# multiple_frequency_divider_1_0.net
KiCad netlist of a schematic drawn in EAGLE
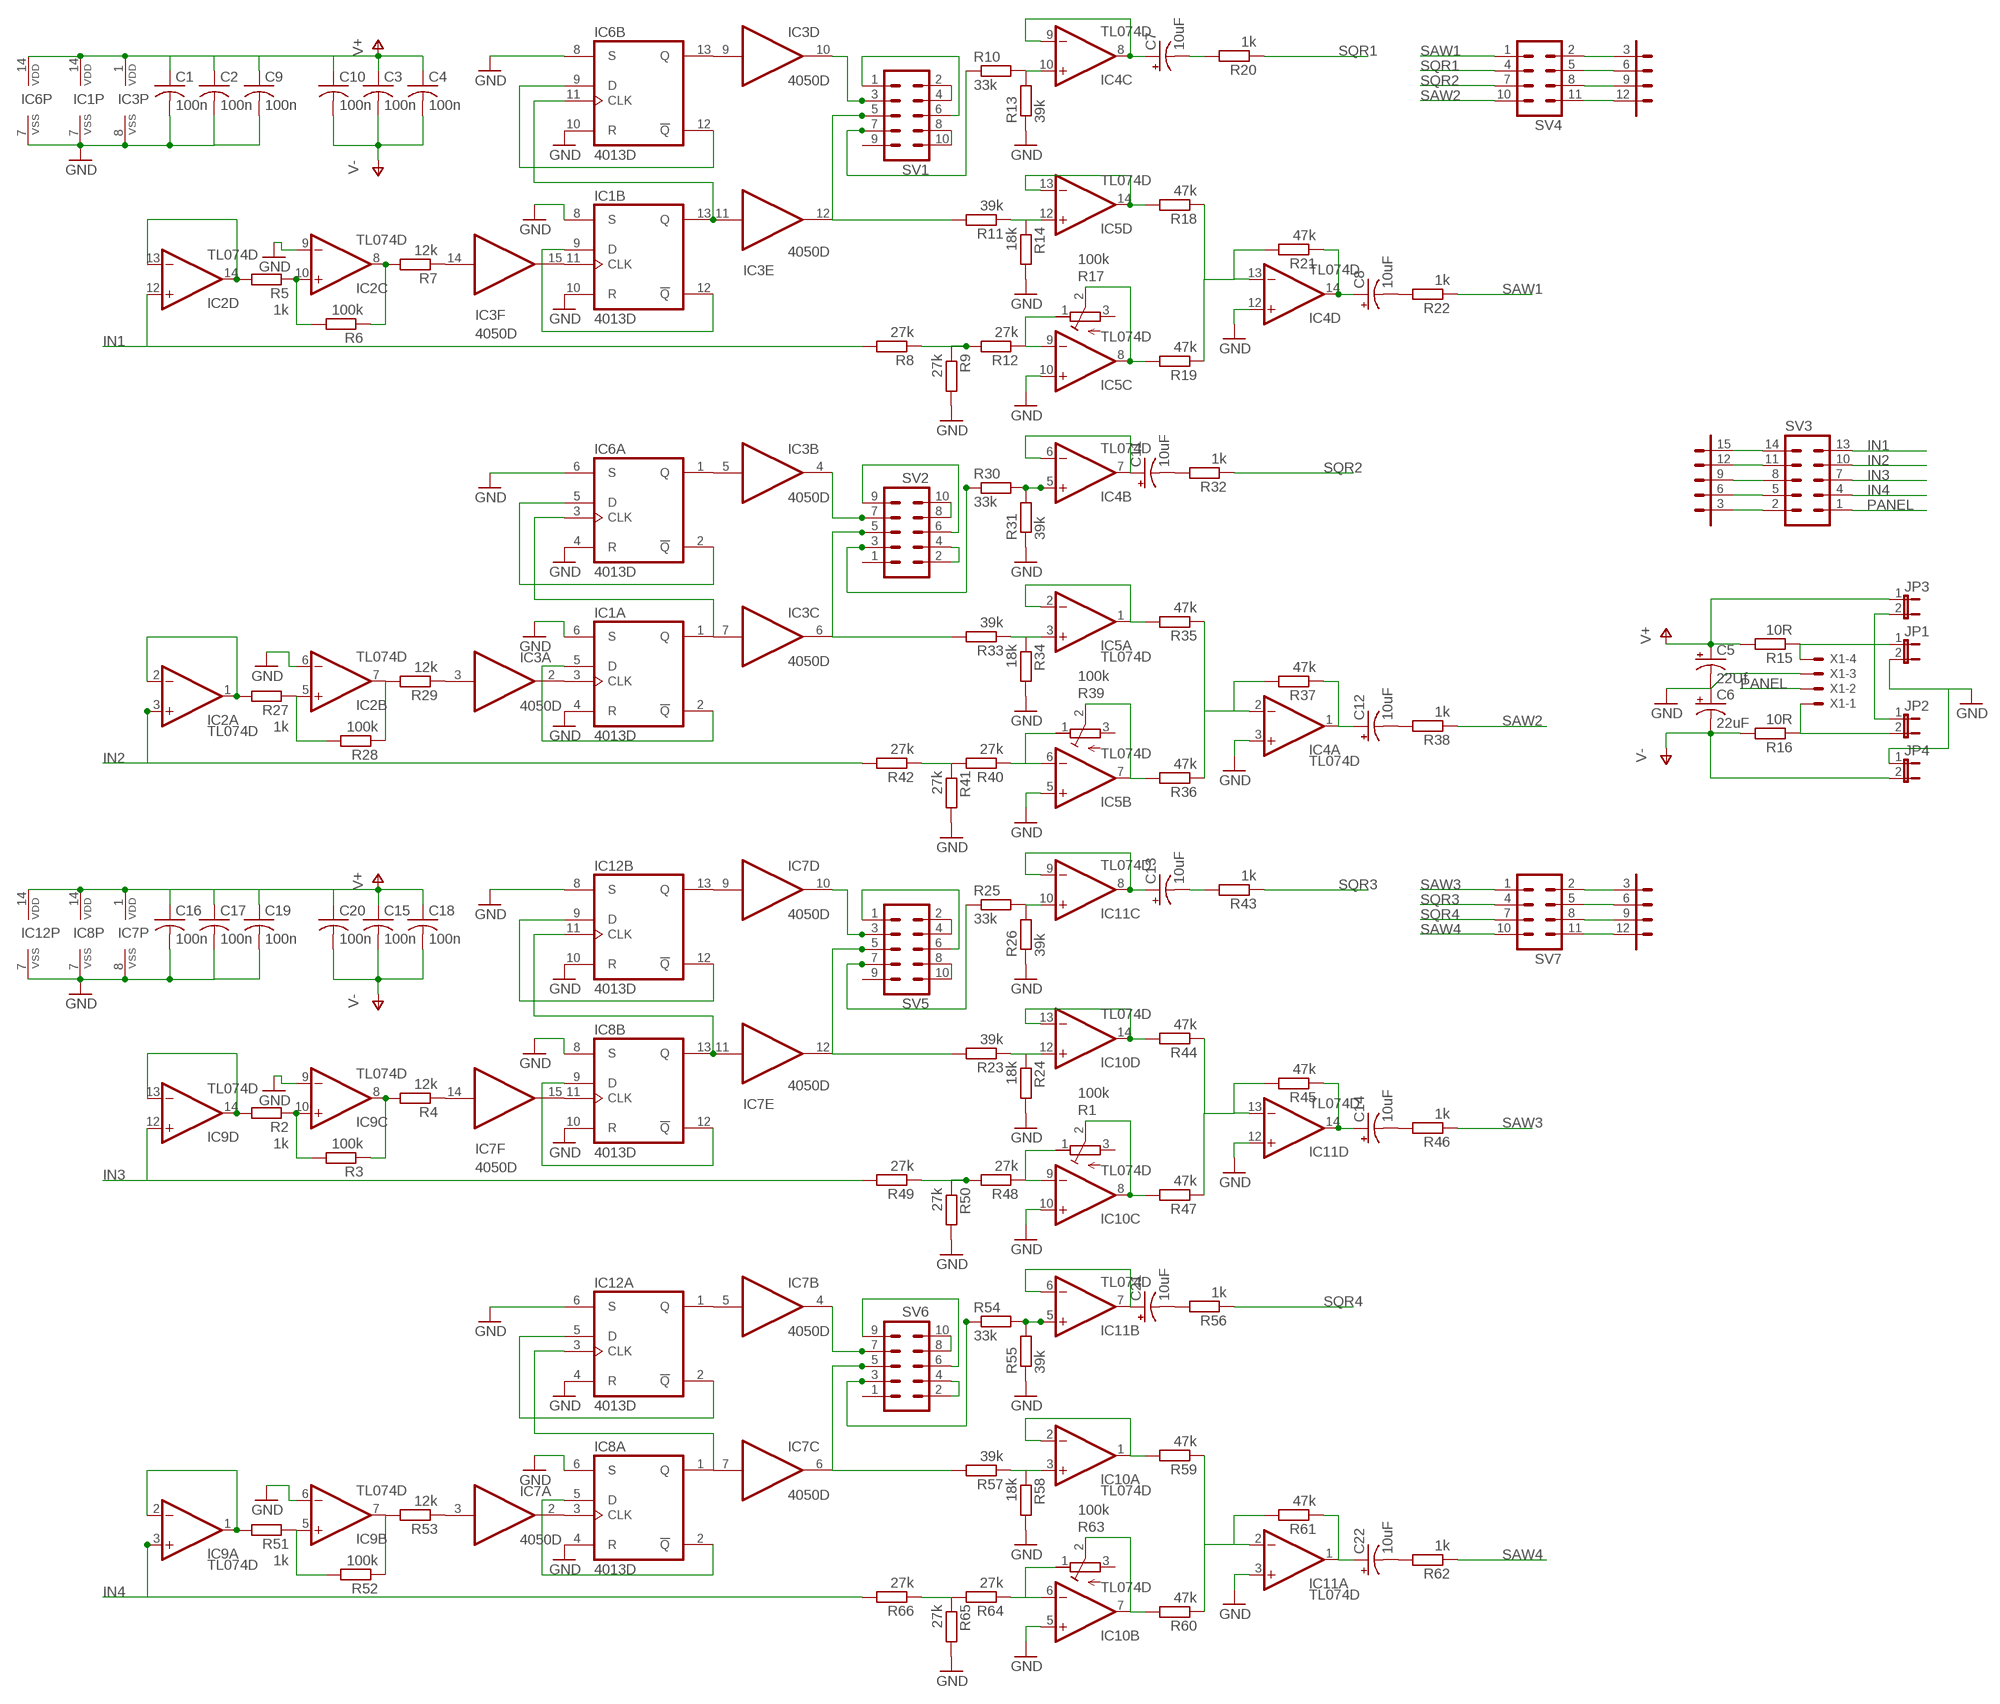
[diagram p0: schematic, sheet 1]

(export (version "E")
  (design (tool "Eeschema 10.0.6"))
  (components
    (comp (ref "C1")
      (value "100n")
      (footprint "eagle-import:C025-024X044")
      (libsource (lib "eagle-import") (part "C-US025-024X044"))
    )
    (comp (ref "C2")
      (value "100n")
      (footprint "eagle-import:C025-024X044")
      (libsource (lib "eagle-import") (part "C-US025-024X044"))
    )
    (comp (ref "C3")
      (value "100n")
      (footprint "eagle-import:C025-024X044")
      (libsource (lib "eagle-import") (part "C-US025-024X044"))
    )
    (comp (ref "C4")
      (value "100n")
      (footprint "eagle-import:C025-024X044")
      (libsource (lib "eagle-import") (part "C-US025-024X044"))
    )
    (comp (ref "C5")
      (value "22Uf")
      (footprint "eagle-import:E2,5-5")
      (libsource (lib "eagle-import") (part "CPOL-USE2.5-5"))
    )
    (comp (ref "C6")
      (value "22uF")
      (footprint "eagle-import:E2,5-5")
      (libsource (lib "eagle-import") (part "CPOL-USE2.5-5"))
    )
    (comp (ref "C7")
      (value "10uF")
      (footprint "eagle-import:E2,5-5")
      (libsource (lib "eagle-import") (part "CPOL-USE2.5-5"))
    )
    (comp (ref "C8")
      (value "10uF")
      (footprint "eagle-import:E2,5-5")
      (libsource (lib "eagle-import") (part "CPOL-USE2.5-5"))
    )
    (comp (ref "C9")
      (value "100n")
      (footprint "eagle-import:C025-024X044")
      (libsource (lib "eagle-import") (part "C-US025-024X044"))
    )
    (comp (ref "C10")
      (value "100n")
      (footprint "eagle-import:C025-024X044")
      (libsource (lib "eagle-import") (part "C-US025-024X044"))
    )
    (comp (ref "C11")
      (value "10uF")
      (footprint "eagle-import:E2,5-5")
      (libsource (lib "eagle-import") (part "CPOL-USE2.5-5"))
    )
    (comp (ref "C12")
      (value "10uF")
      (footprint "eagle-import:E2,5-5")
      (libsource (lib "eagle-import") (part "CPOL-USE2.5-5"))
    )
    (comp (ref "C13")
      (value "10uF")
      (footprint "eagle-import:E2,5-5")
      (libsource (lib "eagle-import") (part "CPOL-USE2.5-5"))
    )
    (comp (ref "C14")
      (value "10uF")
      (footprint "eagle-import:E2,5-5")
      (libsource (lib "eagle-import") (part "CPOL-USE2.5-5"))
    )
    (comp (ref "C15")
      (value "100n")
      (footprint "eagle-import:C025-024X044")
      (libsource (lib "eagle-import") (part "C-US025-024X044"))
    )
    (comp (ref "C16")
      (value "100n")
      (footprint "eagle-import:C025-024X044")
      (libsource (lib "eagle-import") (part "C-US025-024X044"))
    )
    (comp (ref "C17")
      (value "100n")
      (footprint "eagle-import:C025-024X044")
      (libsource (lib "eagle-import") (part "C-US025-024X044"))
    )
    (comp (ref "C18")
      (value "100n")
      (footprint "eagle-import:C025-024X044")
      (libsource (lib "eagle-import") (part "C-US025-024X044"))
    )
    (comp (ref "C19")
      (value "100n")
      (footprint "eagle-import:C025-024X044")
      (libsource (lib "eagle-import") (part "C-US025-024X044"))
    )
    (comp (ref "C20")
      (value "100n")
      (footprint "eagle-import:C025-024X044")
      (libsource (lib "eagle-import") (part "C-US025-024X044"))
    )
    (comp (ref "C21")
      (value "10uF")
      (footprint "eagle-import:E2,5-5")
      (libsource (lib "eagle-import") (part "CPOL-USE2.5-5"))
    )
    (comp (ref "C22")
      (value "10uF")
      (footprint "eagle-import:E2,5-5")
      (libsource (lib "eagle-import") (part "CPOL-USE2.5-5"))
    )
    (comp (ref "IC1")
      (value "4013D")
      (footprint "eagle-import:SO14")
      (libsource (lib "eagle-import") (part "4013D"))
    )
    (comp (ref "IC2")
      (value "TL074D")
      (footprint "eagle-import:SO14")
      (libsource (lib "eagle-import") (part "TL074D"))
    )
    (comp (ref "IC3")
      (value "4050D")
      (footprint "eagle-import:SO16")
      (libsource (lib "eagle-import") (part "4050D"))
    )
    (comp (ref "IC4")
      (value "TL074D")
      (footprint "eagle-import:SO14")
      (libsource (lib "eagle-import") (part "TL074D"))
    )
    (comp (ref "IC5")
      (value "TL074D")
      (footprint "eagle-import:SO14")
      (libsource (lib "eagle-import") (part "TL074D"))
    )
    (comp (ref "IC6")
      (value "4013D")
      (footprint "eagle-import:SO14")
      (libsource (lib "eagle-import") (part "4013D"))
    )
    (comp (ref "IC7")
      (value "4050D")
      (footprint "eagle-import:SO16")
      (libsource (lib "eagle-import") (part "4050D"))
    )
    (comp (ref "IC8")
      (value "4013D")
      (footprint "eagle-import:SO14")
      (libsource (lib "eagle-import") (part "4013D"))
    )
    (comp (ref "IC9")
      (value "TL074D")
      (footprint "eagle-import:SO14")
      (libsource (lib "eagle-import") (part "TL074D"))
    )
    (comp (ref "IC10")
      (value "TL074D")
      (footprint "eagle-import:SO14")
      (libsource (lib "eagle-import") (part "TL074D"))
    )
    (comp (ref "IC11")
      (value "TL074D")
      (footprint "eagle-import:SO14")
      (libsource (lib "eagle-import") (part "TL074D"))
    )
    (comp (ref "IC12")
      (value "4013D")
      (footprint "eagle-import:SO14")
      (libsource (lib "eagle-import") (part "4013D"))
    )
    (comp (ref "JP1")
      (value "JP1E")
      (footprint "eagle-import:JP1")
      (libsource (lib "eagle-import") (part "JP1E"))
    )
    (comp (ref "JP2")
      (value "JP1E")
      (footprint "eagle-import:JP1")
      (libsource (lib "eagle-import") (part "JP1E"))
    )
    (comp (ref "JP3")
      (value "JP1E")
      (footprint "eagle-import:JP1")
      (libsource (lib "eagle-import") (part "JP1E"))
    )
    (comp (ref "JP4")
      (value "JP1E")
      (footprint "eagle-import:JP1")
      (libsource (lib "eagle-import") (part "JP1E"))
    )
    (comp (ref "R1")
      (value "100k")
      (footprint "eagle-import:RTRIMT93YA")
      (libsource (lib "eagle-import") (part "R-TRIMMT93YA"))
    )
    (comp (ref "R2")
      (value "1k")
      (footprint "eagle-import:0204_5")
      (libsource (lib "eagle-import") (part "R-EU_0204/5"))
    )
    (comp (ref "R3")
      (value "100k")
      (footprint "eagle-import:0204_5")
      (libsource (lib "eagle-import") (part "R-EU_0204/5"))
    )
    (comp (ref "R4")
      (value "12k")
      (footprint "eagle-import:0204_5")
      (libsource (lib "eagle-import") (part "R-EU_0204/5"))
    )
    (comp (ref "R5")
      (value "1k")
      (footprint "eagle-import:0204_5")
      (libsource (lib "eagle-import") (part "R-EU_0204/5"))
    )
    (comp (ref "R6")
      (value "100k")
      (footprint "eagle-import:0204_5")
      (libsource (lib "eagle-import") (part "R-EU_0204/5"))
    )
    (comp (ref "R7")
      (value "12k")
      (footprint "eagle-import:0204_5")
      (libsource (lib "eagle-import") (part "R-EU_0204/5"))
    )
    (comp (ref "R8")
      (value "27k")
      (footprint "eagle-import:0204_5")
      (libsource (lib "eagle-import") (part "R-EU_0204/5"))
    )
    (comp (ref "R9")
      (value "27k")
      (footprint "eagle-import:0204_5")
      (libsource (lib "eagle-import") (part "R-EU_0204/5"))
    )
    (comp (ref "R10")
      (value "33k")
      (footprint "eagle-import:0204_5")
      (libsource (lib "eagle-import") (part "R-EU_0204/5"))
    )
    (comp (ref "R11")
      (value "39k")
      (footprint "eagle-import:0204_5")
      (libsource (lib "eagle-import") (part "R-EU_0204/5"))
    )
    (comp (ref "R12")
      (value "27k")
      (footprint "eagle-import:0204_5")
      (libsource (lib "eagle-import") (part "R-EU_0204/5"))
    )
    (comp (ref "R13")
      (value "39k")
      (footprint "eagle-import:0204_5")
      (libsource (lib "eagle-import") (part "R-EU_0204/5"))
    )
    (comp (ref "R14")
      (value "18k")
      (footprint "eagle-import:0204_5")
      (libsource (lib "eagle-import") (part "R-EU_0204/5"))
    )
    (comp (ref "R15")
      (value "10R")
      (footprint "eagle-import:0204_5")
      (libsource (lib "eagle-import") (part "R-EU_0204/5"))
    )
    (comp (ref "R16")
      (value "10R")
      (footprint "eagle-import:0204_5")
      (libsource (lib "eagle-import") (part "R-EU_0204/5"))
    )
    (comp (ref "R17")
      (value "100k")
      (footprint "eagle-import:RTRIMT93YA")
      (libsource (lib "eagle-import") (part "R-TRIMMT93YA"))
    )
    (comp (ref "R18")
      (value "47k")
      (footprint "eagle-import:0204_5")
      (libsource (lib "eagle-import") (part "R-EU_0204/5"))
    )
    (comp (ref "R19")
      (value "47k")
      (footprint "eagle-import:0204_5")
      (libsource (lib "eagle-import") (part "R-EU_0204/5"))
    )
    (comp (ref "R20")
      (value "1k")
      (footprint "eagle-import:0204_5")
      (libsource (lib "eagle-import") (part "R-EU_0204/5"))
    )
    (comp (ref "R21")
      (value "47k")
      (footprint "eagle-import:0204_5")
      (libsource (lib "eagle-import") (part "R-EU_0204/5"))
    )
    (comp (ref "R22")
      (value "1k")
      (footprint "eagle-import:0204_5")
      (libsource (lib "eagle-import") (part "R-EU_0204/5"))
    )
    (comp (ref "R23")
      (value "39k")
      (footprint "eagle-import:0204_5")
      (libsource (lib "eagle-import") (part "R-EU_0204/5"))
    )
    (comp (ref "R24")
      (value "18k")
      (footprint "eagle-import:0204_5")
      (libsource (lib "eagle-import") (part "R-EU_0204/5"))
    )
    (comp (ref "R25")
      (value "33k")
      (footprint "eagle-import:0204_5")
      (libsource (lib "eagle-import") (part "R-EU_0204/5"))
    )
    (comp (ref "R26")
      (value "39k")
      (footprint "eagle-import:0204_5")
      (libsource (lib "eagle-import") (part "R-EU_0204/5"))
    )
    (comp (ref "R27")
      (value "1k")
      (footprint "eagle-import:0204_5")
      (libsource (lib "eagle-import") (part "R-EU_0204/5"))
    )
    (comp (ref "R28")
      (value "100k")
      (footprint "eagle-import:0204_5")
      (libsource (lib "eagle-import") (part "R-EU_0204/5"))
    )
    (comp (ref "R29")
      (value "12k")
      (footprint "eagle-import:0204_5")
      (libsource (lib "eagle-import") (part "R-EU_0204/5"))
    )
    (comp (ref "R30")
      (value "33k")
      (footprint "eagle-import:0204_5")
      (libsource (lib "eagle-import") (part "R-EU_0204/5"))
    )
    (comp (ref "R31")
      (value "39k")
      (footprint "eagle-import:0204_5")
      (libsource (lib "eagle-import") (part "R-EU_0204/5"))
    )
    (comp (ref "R32")
      (value "1k")
      (footprint "eagle-import:0204_5")
      (libsource (lib "eagle-import") (part "R-EU_0204/5"))
    )
    (comp (ref "R33")
      (value "39k")
      (footprint "eagle-import:0204_5")
      (libsource (lib "eagle-import") (part "R-EU_0204/5"))
    )
    (comp (ref "R34")
      (value "18k")
      (footprint "eagle-import:0204_5")
      (libsource (lib "eagle-import") (part "R-EU_0204/5"))
    )
    (comp (ref "R35")
      (value "47k")
      (footprint "eagle-import:0204_5")
      (libsource (lib "eagle-import") (part "R-EU_0204/5"))
    )
    (comp (ref "R36")
      (value "47k")
      (footprint "eagle-import:0204_5")
      (libsource (lib "eagle-import") (part "R-EU_0204/5"))
    )
    (comp (ref "R37")
      (value "47k")
      (footprint "eagle-import:0204_5")
      (libsource (lib "eagle-import") (part "R-EU_0204/5"))
    )
    (comp (ref "R38")
      (value "1k")
      (footprint "eagle-import:0204_5")
      (libsource (lib "eagle-import") (part "R-EU_0204/5"))
    )
    (comp (ref "R39")
      (value "100k")
      (footprint "eagle-import:RTRIMT93YA")
      (libsource (lib "eagle-import") (part "R-TRIMMT93YA"))
    )
    (comp (ref "R40")
      (value "27k")
      (footprint "eagle-import:0204_5")
      (libsource (lib "eagle-import") (part "R-EU_0204/5"))
    )
    (comp (ref "R41")
      (value "27k")
      (footprint "eagle-import:0204_5")
      (libsource (lib "eagle-import") (part "R-EU_0204/5"))
    )
    (comp (ref "R42")
      (value "27k")
      (footprint "eagle-import:0204_5")
      (libsource (lib "eagle-import") (part "R-EU_0204/5"))
    )
    (comp (ref "R43")
      (value "1k")
      (footprint "eagle-import:0204_5")
      (libsource (lib "eagle-import") (part "R-EU_0204/5"))
    )
    (comp (ref "R44")
      (value "47k")
      (footprint "eagle-import:0204_5")
      (libsource (lib "eagle-import") (part "R-EU_0204/5"))
    )
    (comp (ref "R45")
      (value "47k")
      (footprint "eagle-import:0204_5")
      (libsource (lib "eagle-import") (part "R-EU_0204/5"))
    )
    (comp (ref "R46")
      (value "1k")
      (footprint "eagle-import:0204_5")
      (libsource (lib "eagle-import") (part "R-EU_0204/5"))
    )
    (comp (ref "R47")
      (value "47k")
      (footprint "eagle-import:0204_5")
      (libsource (lib "eagle-import") (part "R-EU_0204/5"))
    )
    (comp (ref "R48")
      (value "27k")
      (footprint "eagle-import:0204_5")
      (libsource (lib "eagle-import") (part "R-EU_0204/5"))
    )
    (comp (ref "R49")
      (value "27k")
      (footprint "eagle-import:0204_5")
      (libsource (lib "eagle-import") (part "R-EU_0204/5"))
    )
    (comp (ref "R50")
      (value "27k")
      (footprint "eagle-import:0204_5")
      (libsource (lib "eagle-import") (part "R-EU_0204/5"))
    )
    (comp (ref "R51")
      (value "1k")
      (footprint "eagle-import:0204_5")
      (libsource (lib "eagle-import") (part "R-EU_0204/5"))
    )
    (comp (ref "R52")
      (value "100k")
      (footprint "eagle-import:0204_5")
      (libsource (lib "eagle-import") (part "R-EU_0204/5"))
    )
    (comp (ref "R53")
      (value "12k")
      (footprint "eagle-import:0204_5")
      (libsource (lib "eagle-import") (part "R-EU_0204/5"))
    )
    (comp (ref "R54")
      (value "33k")
      (footprint "eagle-import:0204_5")
      (libsource (lib "eagle-import") (part "R-EU_0204/5"))
    )
    (comp (ref "R55")
      (value "39k")
      (footprint "eagle-import:0204_5")
      (libsource (lib "eagle-import") (part "R-EU_0204/5"))
    )
    (comp (ref "R56")
      (value "1k")
      (footprint "eagle-import:0204_5")
      (libsource (lib "eagle-import") (part "R-EU_0204/5"))
    )
    (comp (ref "R57")
      (value "39k")
      (footprint "eagle-import:0204_5")
      (libsource (lib "eagle-import") (part "R-EU_0204/5"))
    )
    (comp (ref "R58")
      (value "18k")
      (footprint "eagle-import:0204_5")
      (libsource (lib "eagle-import") (part "R-EU_0204/5"))
    )
    (comp (ref "R59")
      (value "47k")
      (footprint "eagle-import:0204_5")
      (libsource (lib "eagle-import") (part "R-EU_0204/5"))
    )
    (comp (ref "R60")
      (value "47k")
      (footprint "eagle-import:0204_5")
      (libsource (lib "eagle-import") (part "R-EU_0204/5"))
    )
    (comp (ref "R61")
      (value "47k")
      (footprint "eagle-import:0204_5")
      (libsource (lib "eagle-import") (part "R-EU_0204/5"))
    )
    (comp (ref "R62")
      (value "1k")
      (footprint "eagle-import:0204_5")
      (libsource (lib "eagle-import") (part "R-EU_0204/5"))
    )
    (comp (ref "R63")
      (value "100k")
      (footprint "eagle-import:RTRIMT93YA")
      (libsource (lib "eagle-import") (part "R-TRIMMT93YA"))
    )
    (comp (ref "R64")
      (value "27k")
      (footprint "eagle-import:0204_5")
      (libsource (lib "eagle-import") (part "R-EU_0204/5"))
    )
    (comp (ref "R65")
      (value "27k")
      (footprint "eagle-import:0204_5")
      (libsource (lib "eagle-import") (part "R-EU_0204/5"))
    )
    (comp (ref "R66")
      (value "27k")
      (footprint "eagle-import:0204_5")
      (libsource (lib "eagle-import") (part "R-EU_0204/5"))
    )
    (comp (ref "SV1")
      (value "MA05-2")
      (footprint "eagle-import:MA05-2")
      (libsource (lib "eagle-import") (part "MA05-2"))
    )
    (comp (ref "SV2")
      (value "MA05-2")
      (footprint "eagle-import:MA05-2")
      (libsource (lib "eagle-import") (part "MA05-2"))
    )
    (comp (ref "SV3")
      (value "MA05-3")
      (footprint "eagle-import:MA05-3")
      (libsource (lib "eagle-import") (part "MA05-3"))
    )
    (comp (ref "SV4")
      (value "MA04-3")
      (footprint "eagle-import:MA04-3")
      (libsource (lib "eagle-import") (part "MA04-3"))
    )
    (comp (ref "SV5")
      (value "MA05-2")
      (footprint "eagle-import:MA05-2")
      (libsource (lib "eagle-import") (part "MA05-2"))
    )
    (comp (ref "SV6")
      (value "MA05-2")
      (footprint "eagle-import:MA05-2")
      (libsource (lib "eagle-import") (part "MA05-2"))
    )
    (comp (ref "SV7")
      (value "MA04-3")
      (footprint "eagle-import:MA04-3")
      (libsource (lib "eagle-import") (part "MA04-3"))
    )
    (comp (ref "X1")
      (value "KK-156-4")
      (footprint "eagle-import:KK-156-4")
      (libsource (lib "eagle-import") (part "KK-156-4"))
    )
  )
  (nets
    (net (code "1") (name "/IN1") (class "Default")
      (node (ref "IC2") (pin "12") (pinfunction "+IN_12") (pintype "input"))
      (node (ref "R8") (pin "2") (pinfunction "2_2") (pintype "passive"))
      (node (ref "SV3") (pin "13") (pinfunction "13_13") (pintype "passive"))
    )
    (net (code "2") (name "/IN2") (class "Default")
      (node (ref "IC2") (pin "3") (pinfunction "+IN_3") (pintype "input"))
      (node (ref "R42") (pin "2") (pinfunction "2_2") (pintype "passive"))
      (node (ref "SV3") (pin "10") (pinfunction "10_10") (pintype "passive"))
    )
    (net (code "3") (name "/IN3") (class "Default")
      (node (ref "IC9") (pin "12") (pinfunction "+IN_12") (pintype "input"))
      (node (ref "R49") (pin "2") (pinfunction "2_2") (pintype "passive"))
      (node (ref "SV3") (pin "7") (pinfunction "7_7") (pintype "passive"))
    )
    (net (code "4") (name "/IN4") (class "Default")
      (node (ref "IC9") (pin "3") (pinfunction "+IN_3") (pintype "input"))
      (node (ref "R66") (pin "2") (pinfunction "2_2") (pintype "passive"))
      (node (ref "SV3") (pin "4") (pinfunction "4_4") (pintype "passive"))
    )
    (net (code "5") (name "/PANEL") (class "Default")
      (node (ref "JP2") (pin "1") (pinfunction "1_1") (pintype "passive"))
      (node (ref "JP3") (pin "2") (pinfunction "2_2") (pintype "passive"))
      (node (ref "SV3") (pin "1") (pinfunction "1_1") (pintype "passive"))
      (node (ref "X1") (pin "2") (pinfunction "S_2") (pintype "passive"))
    )
    (net (code "6") (name "/SAW1") (class "Default")
      (node (ref "R22") (pin "1") (pinfunction "1_1") (pintype "passive"))
      (node (ref "SV4") (pin "1") (pinfunction "1_1") (pintype "passive"))
    )
    (net (code "7") (name "/SAW2") (class "Default")
      (node (ref "R38") (pin "1") (pinfunction "1_1") (pintype "passive"))
      (node (ref "SV4") (pin "10") (pinfunction "10_10") (pintype "passive"))
    )
    (net (code "8") (name "/SAW3") (class "Default")
      (node (ref "R46") (pin "1") (pinfunction "1_1") (pintype "passive"))
      (node (ref "SV7") (pin "1") (pinfunction "1_1") (pintype "passive"))
    )
    (net (code "9") (name "/SAW4") (class "Default")
      (node (ref "R62") (pin "1") (pinfunction "1_1") (pintype "passive"))
      (node (ref "SV7") (pin "10") (pinfunction "10_10") (pintype "passive"))
    )
    (net (code "10") (name "/SQR1") (class "Default")
      (node (ref "R20") (pin "1") (pinfunction "1_1") (pintype "passive"))
      (node (ref "SV4") (pin "4") (pinfunction "4_4") (pintype "passive"))
    )
    (net (code "11") (name "/SQR2") (class "Default")
      (node (ref "R32") (pin "1") (pinfunction "1_1") (pintype "passive"))
      (node (ref "SV4") (pin "7") (pinfunction "7_7") (pintype "passive"))
    )
    (net (code "12") (name "/SQR3") (class "Default")
      (node (ref "R43") (pin "1") (pinfunction "1_1") (pintype "passive"))
      (node (ref "SV7") (pin "4") (pinfunction "4_4") (pintype "passive"))
    )
    (net (code "13") (name "/SQR4") (class "Default")
      (node (ref "R56") (pin "1") (pinfunction "1_1") (pintype "passive"))
      (node (ref "SV7") (pin "7") (pinfunction "7_7") (pintype "passive"))
    )
    (net (code "14") (name "GND") (class "Default")
      (node (ref "C1") (pin "2") (pinfunction "2_2") (pintype "passive"))
      (node (ref "C16") (pin "2") (pinfunction "2_2") (pintype "passive"))
      (node (ref "C17") (pin "2") (pinfunction "2_2") (pintype "passive"))
      (node (ref "C19") (pin "2") (pinfunction "2_2") (pintype "passive"))
      (node (ref "C2") (pin "2") (pinfunction "2_2") (pintype "passive"))
      (node (ref "C5") (pin "-") (pinfunction "-_-") (pintype "passive"))
      (node (ref "C6") (pin "+") (pinfunction "+_+") (pintype "passive"))
      (node (ref "C9") (pin "2") (pinfunction "2_2") (pintype "passive"))
      (node (ref "IC1") (pin "10") (pinfunction "R_10") (pintype "input"))
      (node (ref "IC1") (pin "4") (pinfunction "R_4") (pintype "input"))
      (node (ref "IC1") (pin "6") (pinfunction "S_6") (pintype "input"))
      (node (ref "IC1") (pin "7") (pinfunction "VSS_7") (pintype "power_in"))
      (node (ref "IC1") (pin "8") (pinfunction "S_8") (pintype "input"))
      (node (ref "IC10") (pin "10") (pinfunction "+IN_10") (pintype "input"))
      (node (ref "IC10") (pin "5") (pinfunction "+IN_5") (pintype "input"))
      (node (ref "IC11") (pin "12") (pinfunction "+IN_12") (pintype "input"))
      (node (ref "IC11") (pin "3") (pinfunction "+IN_3") (pintype "input"))
      (node (ref "IC12") (pin "10") (pinfunction "R_10") (pintype "input"))
      (node (ref "IC12") (pin "4") (pinfunction "R_4") (pintype "input"))
      (node (ref "IC12") (pin "6") (pinfunction "S_6") (pintype "input"))
      (node (ref "IC12") (pin "7") (pinfunction "VSS_7") (pintype "power_in"))
      (node (ref "IC12") (pin "8") (pinfunction "S_8") (pintype "input"))
      (node (ref "IC2") (pin "6") (pinfunction "-IN_6") (pintype "input"))
      (node (ref "IC2") (pin "9") (pinfunction "-IN_9") (pintype "input"))
      (node (ref "IC3") (pin "8") (pinfunction "VSS_8") (pintype "power_in"))
      (node (ref "IC4") (pin "12") (pinfunction "+IN_12") (pintype "input"))
      (node (ref "IC4") (pin "3") (pinfunction "+IN_3") (pintype "input"))
      (node (ref "IC5") (pin "10") (pinfunction "+IN_10") (pintype "input"))
      (node (ref "IC5") (pin "5") (pinfunction "+IN_5") (pintype "input"))
      (node (ref "IC6") (pin "10") (pinfunction "R_10") (pintype "input"))
      (node (ref "IC6") (pin "4") (pinfunction "R_4") (pintype "input"))
      (node (ref "IC6") (pin "6") (pinfunction "S_6") (pintype "input"))
      (node (ref "IC6") (pin "7") (pinfunction "VSS_7") (pintype "power_in"))
      (node (ref "IC6") (pin "8") (pinfunction "S_8") (pintype "input"))
      (node (ref "IC7") (pin "8") (pinfunction "VSS_8") (pintype "power_in"))
      (node (ref "IC8") (pin "10") (pinfunction "R_10") (pintype "input"))
      (node (ref "IC8") (pin "4") (pinfunction "R_4") (pintype "input"))
      (node (ref "IC8") (pin "6") (pinfunction "S_6") (pintype "input"))
      (node (ref "IC8") (pin "7") (pinfunction "VSS_7") (pintype "power_in"))
      (node (ref "IC8") (pin "8") (pinfunction "S_8") (pintype "input"))
      (node (ref "IC9") (pin "6") (pinfunction "-IN_6") (pintype "input"))
      (node (ref "IC9") (pin "9") (pinfunction "-IN_9") (pintype "input"))
      (node (ref "JP1") (pin "2") (pinfunction "2_2") (pintype "passive"))
      (node (ref "JP4") (pin "1") (pinfunction "1_1") (pintype "passive"))
      (node (ref "R13") (pin "1") (pinfunction "1_1") (pintype "passive"))
      (node (ref "R14") (pin "2") (pinfunction "2_2") (pintype "passive"))
      (node (ref "R24") (pin "2") (pinfunction "2_2") (pintype "passive"))
      (node (ref "R26") (pin "1") (pinfunction "1_1") (pintype "passive"))
      (node (ref "R31") (pin "1") (pinfunction "1_1") (pintype "passive"))
      (node (ref "R34") (pin "2") (pinfunction "2_2") (pintype "passive"))
      (node (ref "R41") (pin "2") (pinfunction "2_2") (pintype "passive"))
      (node (ref "R50") (pin "2") (pinfunction "2_2") (pintype "passive"))
      (node (ref "R55") (pin "1") (pinfunction "1_1") (pintype "passive"))
      (node (ref "R58") (pin "2") (pinfunction "2_2") (pintype "passive"))
      (node (ref "R65") (pin "2") (pinfunction "2_2") (pintype "passive"))
      (node (ref "R9") (pin "2") (pinfunction "2_2") (pintype "passive"))
      (node (ref "X1") (pin "3") (pinfunction "S_3") (pintype "passive"))
    )
    (net (code "15") (name "Net-(C7-Pad-)") (class "Default")
      (node (ref "C7") (pin "-") (pinfunction "-_-") (pintype "passive"))
      (node (ref "R20") (pin "2") (pinfunction "2_2") (pintype "passive"))
    )
    (net (code "16") (name "Net-(C8-Pad-)") (class "Default")
      (node (ref "C8") (pin "-") (pinfunction "-_-") (pintype "passive"))
      (node (ref "R22") (pin "2") (pinfunction "2_2") (pintype "passive"))
    )
    (net (code "17") (name "Net-(C11-Pad-)") (class "Default")
      (node (ref "C11") (pin "-") (pinfunction "-_-") (pintype "passive"))
      (node (ref "R32") (pin "2") (pinfunction "2_2") (pintype "passive"))
    )
    (net (code "18") (name "Net-(C12-Pad-)") (class "Default")
      (node (ref "C12") (pin "-") (pinfunction "-_-") (pintype "passive"))
      (node (ref "R38") (pin "2") (pinfunction "2_2") (pintype "passive"))
    )
    (net (code "19") (name "Net-(C13-Pad-)") (class "Default")
      (node (ref "C13") (pin "-") (pinfunction "-_-") (pintype "passive"))
      (node (ref "R43") (pin "2") (pinfunction "2_2") (pintype "passive"))
    )
    (net (code "20") (name "Net-(C14-Pad-)") (class "Default")
      (node (ref "C14") (pin "-") (pinfunction "-_-") (pintype "passive"))
      (node (ref "R46") (pin "2") (pinfunction "2_2") (pintype "passive"))
    )
    (net (code "21") (name "Net-(C21-Pad-)") (class "Default")
      (node (ref "C21") (pin "-") (pinfunction "-_-") (pintype "passive"))
      (node (ref "R56") (pin "2") (pinfunction "2_2") (pintype "passive"))
    )
    (net (code "22") (name "Net-(C22-Pad-)") (class "Default")
      (node (ref "C22") (pin "-") (pinfunction "-_-") (pintype "passive"))
      (node (ref "R62") (pin "2") (pinfunction "2_2") (pintype "passive"))
    )
    (net (code "23") (name "Net-(IC1A-CLK)") (class "Default")
      (node (ref "IC1") (pin "3") (pinfunction "CLK_3") (pintype "input"))
      (node (ref "IC3") (pin "2") (pinfunction "O_2") (pintype "output"))
    )
    (net (code "24") (name "Net-(IC1A-D)") (class "Default")
      (node (ref "IC1") (pin "2") (pinfunction "~{Q}_2") (pintype "output"))
      (node (ref "IC1") (pin "5") (pinfunction "D_5") (pintype "input"))
    )
    (net (code "25") (name "Net-(IC1A-Q)") (class "Default")
      (node (ref "IC1") (pin "1") (pinfunction "Q_1") (pintype "output"))
      (node (ref "IC3") (pin "7") (pinfunction "I_7") (pintype "input"))
      (node (ref "IC6") (pin "3") (pinfunction "CLK_3") (pintype "input"))
    )
    (net (code "26") (name "Net-(IC1B-CLK)") (class "Default")
      (node (ref "IC1") (pin "11") (pinfunction "CLK_11") (pintype "input"))
      (node (ref "IC3") (pin "15") (pinfunction "O_15") (pintype "output"))
    )
    (net (code "27") (name "Net-(IC1B-D)") (class "Default")
      (node (ref "IC1") (pin "12") (pinfunction "~{Q}_12") (pintype "output"))
      (node (ref "IC1") (pin "9") (pinfunction "D_9") (pintype "input"))
    )
    (net (code "28") (name "Net-(IC1B-Q)") (class "Default")
      (node (ref "IC1") (pin "13") (pinfunction "Q_13") (pintype "output"))
      (node (ref "IC3") (pin "11") (pinfunction "I_11") (pintype "input"))
      (node (ref "IC6") (pin "11") (pinfunction "CLK_11") (pintype "input"))
    )
    (net (code "29") (name "Net-(IC2A--IN)") (class "Default")
      (node (ref "IC2") (pin "1") (pinfunction "OUT_1") (pintype "output"))
      (node (ref "IC2") (pin "2") (pinfunction "-IN_2") (pintype "input"))
      (node (ref "R27") (pin "2") (pinfunction "2_2") (pintype "passive"))
    )
    (net (code "30") (name "Net-(IC2B-+IN)") (class "Default")
      (node (ref "IC2") (pin "5") (pinfunction "+IN_5") (pintype "input"))
      (node (ref "R27") (pin "1") (pinfunction "1_1") (pintype "passive"))
      (node (ref "R28") (pin "2") (pinfunction "2_2") (pintype "passive"))
    )
    (net (code "31") (name "Net-(IC2B-OUT)") (class "Default")
      (node (ref "IC2") (pin "7") (pinfunction "OUT_7") (pintype "output"))
      (node (ref "R28") (pin "1") (pinfunction "1_1") (pintype "passive"))
      (node (ref "R29") (pin "2") (pinfunction "2_2") (pintype "passive"))
    )
    (net (code "32") (name "Net-(IC2C-+IN)") (class "Default")
      (node (ref "IC2") (pin "10") (pinfunction "+IN_10") (pintype "input"))
      (node (ref "R5") (pin "1") (pinfunction "1_1") (pintype "passive"))
      (node (ref "R6") (pin "2") (pinfunction "2_2") (pintype "passive"))
    )
    (net (code "33") (name "Net-(IC2C-OUT)") (class "Default")
      (node (ref "IC2") (pin "8") (pinfunction "OUT_8") (pintype "output"))
      (node (ref "R6") (pin "1") (pinfunction "1_1") (pintype "passive"))
      (node (ref "R7") (pin "2") (pinfunction "2_2") (pintype "passive"))
    )
    (net (code "34") (name "Net-(IC2D--IN)") (class "Default")
      (node (ref "IC2") (pin "13") (pinfunction "-IN_13") (pintype "input"))
      (node (ref "IC2") (pin "14") (pinfunction "OUT_14") (pintype "output"))
      (node (ref "R5") (pin "2") (pinfunction "2_2") (pintype "passive"))
    )
    (net (code "35") (name "Net-(IC3A-I)") (class "Default")
      (node (ref "IC3") (pin "3") (pinfunction "I_3") (pintype "input"))
      (node (ref "R29") (pin "1") (pinfunction "1_1") (pintype "passive"))
    )
    (net (code "36") (name "Net-(IC3B-I)") (class "Default")
      (node (ref "IC3") (pin "5") (pinfunction "I_5") (pintype "input"))
      (node (ref "IC6") (pin "1") (pinfunction "Q_1") (pintype "output"))
    )
    (net (code "37") (name "Net-(IC3B-O)") (class "Default")
      (node (ref "IC3") (pin "4") (pinfunction "O_4") (pintype "output"))
      (node (ref "SV2") (pin "7") (pinfunction "7_7") (pintype "passive"))
    )
    (net (code "38") (name "Net-(IC3C-O)") (class "Default")
      (node (ref "IC3") (pin "6") (pinfunction "O_6") (pintype "output"))
      (node (ref "R33") (pin "2") (pinfunction "2_2") (pintype "passive"))
      (node (ref "SV2") (pin "5") (pinfunction "5_5") (pintype "passive"))
    )
    (net (code "39") (name "Net-(IC3D-I)") (class "Default")
      (node (ref "IC3") (pin "9") (pinfunction "I_9") (pintype "input"))
      (node (ref "IC6") (pin "13") (pinfunction "Q_13") (pintype "output"))
    )
    (net (code "40") (name "Net-(IC3D-O)") (class "Default")
      (node (ref "IC3") (pin "10") (pinfunction "O_10") (pintype "output"))
      (node (ref "SV1") (pin "3") (pinfunction "3_3") (pintype "passive"))
    )
    (net (code "41") (name "Net-(IC3E-O)") (class "Default")
      (node (ref "IC3") (pin "12") (pinfunction "O_12") (pintype "output"))
      (node (ref "R11") (pin "2") (pinfunction "2_2") (pintype "passive"))
      (node (ref "SV1") (pin "5") (pinfunction "5_5") (pintype "passive"))
    )
    (net (code "42") (name "Net-(IC3F-I)") (class "Default")
      (node (ref "IC3") (pin "14") (pinfunction "I_14") (pintype "input"))
      (node (ref "R7") (pin "1") (pinfunction "1_1") (pintype "passive"))
    )
    (net (code "43") (name "Net-(IC4A--IN)") (class "Default")
      (node (ref "IC4") (pin "2") (pinfunction "-IN_2") (pintype "input"))
      (node (ref "R35") (pin "1") (pinfunction "1_1") (pintype "passive"))
      (node (ref "R36") (pin "1") (pinfunction "1_1") (pintype "passive"))
      (node (ref "R37") (pin "2") (pinfunction "2_2") (pintype "passive"))
    )
    (net (code "44") (name "Net-(IC4A-OUT)") (class "Default")
      (node (ref "C12") (pin "+") (pinfunction "+_+") (pintype "passive"))
      (node (ref "IC4") (pin "1") (pinfunction "OUT_1") (pintype "output"))
      (node (ref "R37") (pin "1") (pinfunction "1_1") (pintype "passive"))
    )
    (net (code "45") (name "Net-(IC4B-+IN)") (class "Default")
      (node (ref "IC4") (pin "5") (pinfunction "+IN_5") (pintype "input"))
      (node (ref "R30") (pin "2") (pinfunction "2_2") (pintype "passive"))
      (node (ref "R31") (pin "2") (pinfunction "2_2") (pintype "passive"))
    )
    (net (code "46") (name "Net-(IC4B--IN)") (class "Default")
      (node (ref "C11") (pin "+") (pinfunction "+_+") (pintype "passive"))
      (node (ref "IC4") (pin "6") (pinfunction "-IN_6") (pintype "input"))
      (node (ref "IC4") (pin "7") (pinfunction "OUT_7") (pintype "output"))
    )
    (net (code "47") (name "Net-(IC4C-+IN)") (class "Default")
      (node (ref "IC4") (pin "10") (pinfunction "+IN_10") (pintype "input"))
      (node (ref "R10") (pin "2") (pinfunction "2_2") (pintype "passive"))
      (node (ref "R13") (pin "2") (pinfunction "2_2") (pintype "passive"))
    )
    (net (code "48") (name "Net-(IC4C--IN)") (class "Default")
      (node (ref "C7") (pin "+") (pinfunction "+_+") (pintype "passive"))
      (node (ref "IC4") (pin "8") (pinfunction "OUT_8") (pintype "output"))
      (node (ref "IC4") (pin "9") (pinfunction "-IN_9") (pintype "input"))
    )
    (net (code "49") (name "Net-(IC4D--IN)") (class "Default")
      (node (ref "IC4") (pin "13") (pinfunction "-IN_13") (pintype "input"))
      (node (ref "R18") (pin "1") (pinfunction "1_1") (pintype "passive"))
      (node (ref "R19") (pin "1") (pinfunction "1_1") (pintype "passive"))
      (node (ref "R21") (pin "2") (pinfunction "2_2") (pintype "passive"))
    )
    (net (code "50") (name "Net-(IC4D-OUT)") (class "Default")
      (node (ref "C8") (pin "+") (pinfunction "+_+") (pintype "passive"))
      (node (ref "IC4") (pin "14") (pinfunction "OUT_14") (pintype "output"))
      (node (ref "R21") (pin "1") (pinfunction "1_1") (pintype "passive"))
    )
    (net (code "51") (name "Net-(IC5A-+IN)") (class "Default")
      (node (ref "IC5") (pin "3") (pinfunction "+IN_3") (pintype "input"))
      (node (ref "R33") (pin "1") (pinfunction "1_1") (pintype "passive"))
      (node (ref "R34") (pin "1") (pinfunction "1_1") (pintype "passive"))
    )
    (net (code "52") (name "Net-(IC5A--IN)") (class "Default")
      (node (ref "IC5") (pin "1") (pinfunction "OUT_1") (pintype "output"))
      (node (ref "IC5") (pin "2") (pinfunction "-IN_2") (pintype "input"))
      (node (ref "R35") (pin "2") (pinfunction "2_2") (pintype "passive"))
    )
    (net (code "53") (name "Net-(IC5B--IN)") (class "Default")
      (node (ref "IC5") (pin "6") (pinfunction "-IN_6") (pintype "input"))
      (node (ref "R39") (pin "1") (pinfunction "A_1") (pintype "passive"))
      (node (ref "R40") (pin "1") (pinfunction "1_1") (pintype "passive"))
    )
    (net (code "54") (name "Net-(IC5B-OUT)") (class "Default")
      (node (ref "IC5") (pin "7") (pinfunction "OUT_7") (pintype "output"))
      (node (ref "R36") (pin "2") (pinfunction "2_2") (pintype "passive"))
      (node (ref "R39") (pin "2") (pinfunction "S_2") (pintype "passive"))
    )
    (net (code "55") (name "Net-(IC5C--IN)") (class "Default")
      (node (ref "IC5") (pin "9") (pinfunction "-IN_9") (pintype "input"))
      (node (ref "R12") (pin "1") (pinfunction "1_1") (pintype "passive"))
      (node (ref "R17") (pin "1") (pinfunction "A_1") (pintype "passive"))
    )
    (net (code "56") (name "Net-(IC5C-OUT)") (class "Default")
      (node (ref "IC5") (pin "8") (pinfunction "OUT_8") (pintype "output"))
      (node (ref "R17") (pin "2") (pinfunction "S_2") (pintype "passive"))
      (node (ref "R19") (pin "2") (pinfunction "2_2") (pintype "passive"))
    )
    (net (code "57") (name "Net-(IC5D-+IN)") (class "Default")
      (node (ref "IC5") (pin "12") (pinfunction "+IN_12") (pintype "input"))
      (node (ref "R11") (pin "1") (pinfunction "1_1") (pintype "passive"))
      (node (ref "R14") (pin "1") (pinfunction "1_1") (pintype "passive"))
    )
    (net (code "58") (name "Net-(IC5D--IN)") (class "Default")
      (node (ref "IC5") (pin "13") (pinfunction "-IN_13") (pintype "input"))
      (node (ref "IC5") (pin "14") (pinfunction "OUT_14") (pintype "output"))
      (node (ref "R18") (pin "2") (pinfunction "2_2") (pintype "passive"))
    )
    (net (code "59") (name "Net-(IC6A-D)") (class "Default")
      (node (ref "IC6") (pin "2") (pinfunction "~{Q}_2") (pintype "output"))
      (node (ref "IC6") (pin "5") (pinfunction "D_5") (pintype "input"))
    )
    (net (code "60") (name "Net-(IC6B-D)") (class "Default")
      (node (ref "IC6") (pin "12") (pinfunction "~{Q}_12") (pintype "output"))
      (node (ref "IC6") (pin "9") (pinfunction "D_9") (pintype "input"))
    )
    (net (code "61") (name "Net-(IC7A-I)") (class "Default")
      (node (ref "IC7") (pin "3") (pinfunction "I_3") (pintype "input"))
      (node (ref "R53") (pin "1") (pinfunction "1_1") (pintype "passive"))
    )
    (net (code "62") (name "Net-(IC7A-O)") (class "Default")
      (node (ref "IC7") (pin "2") (pinfunction "O_2") (pintype "output"))
      (node (ref "IC8") (pin "3") (pinfunction "CLK_3") (pintype "input"))
    )
    (net (code "63") (name "Net-(IC7B-O)") (class "Default")
      (node (ref "IC7") (pin "4") (pinfunction "O_4") (pintype "output"))
      (node (ref "SV6") (pin "7") (pinfunction "7_7") (pintype "passive"))
    )
    (net (code "64") (name "Net-(IC7C-O)") (class "Default")
      (node (ref "IC7") (pin "6") (pinfunction "O_6") (pintype "output"))
      (node (ref "R57") (pin "2") (pinfunction "2_2") (pintype "passive"))
      (node (ref "SV6") (pin "5") (pinfunction "5_5") (pintype "passive"))
    )
    (net (code "65") (name "Net-(IC7D-O)") (class "Default")
      (node (ref "IC7") (pin "10") (pinfunction "O_10") (pintype "output"))
      (node (ref "SV5") (pin "3") (pinfunction "3_3") (pintype "passive"))
    )
    (net (code "66") (name "Net-(IC7E-O)") (class "Default")
      (node (ref "IC7") (pin "12") (pinfunction "O_12") (pintype "output"))
      (node (ref "R23") (pin "2") (pinfunction "2_2") (pintype "passive"))
      (node (ref "SV5") (pin "5") (pinfunction "5_5") (pintype "passive"))
    )
    (net (code "67") (name "Net-(IC7F-I)") (class "Default")
      (node (ref "IC7") (pin "14") (pinfunction "I_14") (pintype "input"))
      (node (ref "R4") (pin "1") (pinfunction "1_1") (pintype "passive"))
    )
    (net (code "68") (name "Net-(IC7F-O)") (class "Default")
      (node (ref "IC7") (pin "15") (pinfunction "O_15") (pintype "output"))
      (node (ref "IC8") (pin "11") (pinfunction "CLK_11") (pintype "input"))
    )
    (net (code "69") (name "Net-(IC8A-D)") (class "Default")
      (node (ref "IC8") (pin "2") (pinfunction "~{Q}_2") (pintype "output"))
      (node (ref "IC8") (pin "5") (pinfunction "D_5") (pintype "input"))
    )
    (net (code "70") (name "Net-(IC8B-D)") (class "Default")
      (node (ref "IC8") (pin "12") (pinfunction "~{Q}_12") (pintype "output"))
      (node (ref "IC8") (pin "9") (pinfunction "D_9") (pintype "input"))
    )
    (net (code "71") (name "Net-(IC9A--IN)") (class "Default")
      (node (ref "IC9") (pin "1") (pinfunction "OUT_1") (pintype "output"))
      (node (ref "IC9") (pin "2") (pinfunction "-IN_2") (pintype "input"))
      (node (ref "R51") (pin "2") (pinfunction "2_2") (pintype "passive"))
    )
    (net (code "72") (name "Net-(IC9B-+IN)") (class "Default")
      (node (ref "IC9") (pin "5") (pinfunction "+IN_5") (pintype "input"))
      (node (ref "R51") (pin "1") (pinfunction "1_1") (pintype "passive"))
      (node (ref "R52") (pin "2") (pinfunction "2_2") (pintype "passive"))
    )
    (net (code "73") (name "Net-(IC9B-OUT)") (class "Default")
      (node (ref "IC9") (pin "7") (pinfunction "OUT_7") (pintype "output"))
      (node (ref "R52") (pin "1") (pinfunction "1_1") (pintype "passive"))
      (node (ref "R53") (pin "2") (pinfunction "2_2") (pintype "passive"))
    )
    (net (code "74") (name "Net-(IC9C-+IN)") (class "Default")
      (node (ref "IC9") (pin "10") (pinfunction "+IN_10") (pintype "input"))
      (node (ref "R2") (pin "1") (pinfunction "1_1") (pintype "passive"))
      (node (ref "R3") (pin "2") (pinfunction "2_2") (pintype "passive"))
    )
    (net (code "75") (name "Net-(IC9C-OUT)") (class "Default")
      (node (ref "IC9") (pin "8") (pinfunction "OUT_8") (pintype "output"))
      (node (ref "R3") (pin "1") (pinfunction "1_1") (pintype "passive"))
      (node (ref "R4") (pin "2") (pinfunction "2_2") (pintype "passive"))
    )
    (net (code "76") (name "Net-(IC9D--IN)") (class "Default")
      (node (ref "IC9") (pin "13") (pinfunction "-IN_13") (pintype "input"))
      (node (ref "IC9") (pin "14") (pinfunction "OUT_14") (pintype "output"))
      (node (ref "R2") (pin "2") (pinfunction "2_2") (pintype "passive"))
    )
    (net (code "77") (name "Net-(IC10A-+IN)") (class "Default")
      (node (ref "IC10") (pin "3") (pinfunction "+IN_3") (pintype "input"))
      (node (ref "R57") (pin "1") (pinfunction "1_1") (pintype "passive"))
      (node (ref "R58") (pin "1") (pinfunction "1_1") (pintype "passive"))
    )
    (net (code "78") (name "Net-(IC10A--IN)") (class "Default")
      (node (ref "IC10") (pin "1") (pinfunction "OUT_1") (pintype "output"))
      (node (ref "IC10") (pin "2") (pinfunction "-IN_2") (pintype "input"))
      (node (ref "R59") (pin "2") (pinfunction "2_2") (pintype "passive"))
    )
    (net (code "79") (name "Net-(IC10B--IN)") (class "Default")
      (node (ref "IC10") (pin "6") (pinfunction "-IN_6") (pintype "input"))
      (node (ref "R63") (pin "1") (pinfunction "A_1") (pintype "passive"))
      (node (ref "R64") (pin "1") (pinfunction "1_1") (pintype "passive"))
    )
    (net (code "80") (name "Net-(IC10B-OUT)") (class "Default")
      (node (ref "IC10") (pin "7") (pinfunction "OUT_7") (pintype "output"))
      (node (ref "R60") (pin "2") (pinfunction "2_2") (pintype "passive"))
      (node (ref "R63") (pin "2") (pinfunction "S_2") (pintype "passive"))
    )
    (net (code "81") (name "Net-(IC10C--IN)") (class "Default")
      (node (ref "IC10") (pin "9") (pinfunction "-IN_9") (pintype "input"))
      (node (ref "R1") (pin "1") (pinfunction "A_1") (pintype "passive"))
      (node (ref "R48") (pin "1") (pinfunction "1_1") (pintype "passive"))
    )
    (net (code "82") (name "Net-(IC10C-OUT)") (class "Default")
      (node (ref "IC10") (pin "8") (pinfunction "OUT_8") (pintype "output"))
      (node (ref "R1") (pin "2") (pinfunction "S_2") (pintype "passive"))
      (node (ref "R47") (pin "2") (pinfunction "2_2") (pintype "passive"))
    )
    (net (code "83") (name "Net-(IC10D-+IN)") (class "Default")
      (node (ref "IC10") (pin "12") (pinfunction "+IN_12") (pintype "input"))
      (node (ref "R23") (pin "1") (pinfunction "1_1") (pintype "passive"))
      (node (ref "R24") (pin "1") (pinfunction "1_1") (pintype "passive"))
    )
    (net (code "84") (name "Net-(IC10D--IN)") (class "Default")
      (node (ref "IC10") (pin "13") (pinfunction "-IN_13") (pintype "input"))
      (node (ref "IC10") (pin "14") (pinfunction "OUT_14") (pintype "output"))
      (node (ref "R44") (pin "2") (pinfunction "2_2") (pintype "passive"))
    )
    (net (code "85") (name "Net-(IC11A--IN)") (class "Default")
      (node (ref "IC11") (pin "2") (pinfunction "-IN_2") (pintype "input"))
      (node (ref "R59") (pin "1") (pinfunction "1_1") (pintype "passive"))
      (node (ref "R60") (pin "1") (pinfunction "1_1") (pintype "passive"))
      (node (ref "R61") (pin "2") (pinfunction "2_2") (pintype "passive"))
    )
    (net (code "86") (name "Net-(IC11A-OUT)") (class "Default")
      (node (ref "C22") (pin "+") (pinfunction "+_+") (pintype "passive"))
      (node (ref "IC11") (pin "1") (pinfunction "OUT_1") (pintype "output"))
      (node (ref "R61") (pin "1") (pinfunction "1_1") (pintype "passive"))
    )
    (net (code "87") (name "Net-(IC11B-+IN)") (class "Default")
      (node (ref "IC11") (pin "5") (pinfunction "+IN_5") (pintype "input"))
      (node (ref "R54") (pin "2") (pinfunction "2_2") (pintype "passive"))
      (node (ref "R55") (pin "2") (pinfunction "2_2") (pintype "passive"))
    )
    (net (code "88") (name "Net-(IC11B--IN)") (class "Default")
      (node (ref "C21") (pin "+") (pinfunction "+_+") (pintype "passive"))
      (node (ref "IC11") (pin "6") (pinfunction "-IN_6") (pintype "input"))
      (node (ref "IC11") (pin "7") (pinfunction "OUT_7") (pintype "output"))
    )
    (net (code "89") (name "Net-(IC11C-+IN)") (class "Default")
      (node (ref "IC11") (pin "10") (pinfunction "+IN_10") (pintype "input"))
      (node (ref "R25") (pin "2") (pinfunction "2_2") (pintype "passive"))
      (node (ref "R26") (pin "2") (pinfunction "2_2") (pintype "passive"))
    )
    (net (code "90") (name "Net-(IC11C--IN)") (class "Default")
      (node (ref "C13") (pin "+") (pinfunction "+_+") (pintype "passive"))
      (node (ref "IC11") (pin "8") (pinfunction "OUT_8") (pintype "output"))
      (node (ref "IC11") (pin "9") (pinfunction "-IN_9") (pintype "input"))
    )
    (net (code "91") (name "Net-(IC11D--IN)") (class "Default")
      (node (ref "IC11") (pin "13") (pinfunction "-IN_13") (pintype "input"))
      (node (ref "R44") (pin "1") (pinfunction "1_1") (pintype "passive"))
      (node (ref "R45") (pin "2") (pinfunction "2_2") (pintype "passive"))
      (node (ref "R47") (pin "1") (pinfunction "1_1") (pintype "passive"))
    )
    (net (code "92") (name "Net-(IC11D-OUT)") (class "Default")
      (node (ref "C14") (pin "+") (pinfunction "+_+") (pintype "passive"))
      (node (ref "IC11") (pin "14") (pinfunction "OUT_14") (pintype "output"))
      (node (ref "R45") (pin "1") (pinfunction "1_1") (pintype "passive"))
    )
    (net (code "93") (name "Net-(IC12A-CLK)") (class "Default")
      (node (ref "IC12") (pin "3") (pinfunction "CLK_3") (pintype "input"))
      (node (ref "IC7") (pin "7") (pinfunction "I_7") (pintype "input"))
      (node (ref "IC8") (pin "1") (pinfunction "Q_1") (pintype "output"))
    )
    (net (code "94") (name "Net-(IC12A-D)") (class "Default")
      (node (ref "IC12") (pin "2") (pinfunction "~{Q}_2") (pintype "output"))
      (node (ref "IC12") (pin "5") (pinfunction "D_5") (pintype "input"))
    )
    (net (code "95") (name "Net-(IC12A-Q)") (class "Default")
      (node (ref "IC12") (pin "1") (pinfunction "Q_1") (pintype "output"))
      (node (ref "IC7") (pin "5") (pinfunction "I_5") (pintype "input"))
    )
    (net (code "96") (name "Net-(IC12B-CLK)") (class "Default")
      (node (ref "IC12") (pin "11") (pinfunction "CLK_11") (pintype "input"))
      (node (ref "IC7") (pin "11") (pinfunction "I_11") (pintype "input"))
      (node (ref "IC8") (pin "13") (pinfunction "Q_13") (pintype "output"))
    )
    (net (code "97") (name "Net-(IC12B-D)") (class "Default")
      (node (ref "IC12") (pin "12") (pinfunction "~{Q}_12") (pintype "output"))
      (node (ref "IC12") (pin "9") (pinfunction "D_9") (pintype "input"))
    )
    (net (code "98") (name "Net-(IC12B-Q)") (class "Default")
      (node (ref "IC12") (pin "13") (pinfunction "Q_13") (pintype "output"))
      (node (ref "IC7") (pin "9") (pinfunction "I_9") (pintype "input"))
    )
    (net (code "99") (name "Net-(R10-Pad1)") (class "Default")
      (node (ref "R10") (pin "1") (pinfunction "1_1") (pintype "passive"))
      (node (ref "SV1") (pin "7") (pinfunction "7_7") (pintype "passive"))
    )
    (net (code "100") (name "Net-(R12-Pad2)") (class "Default")
      (node (ref "R12") (pin "2") (pinfunction "2_2") (pintype "passive"))
      (node (ref "R8") (pin "1") (pinfunction "1_1") (pintype "passive"))
      (node (ref "R9") (pin "1") (pinfunction "1_1") (pintype "passive"))
    )
    (net (code "101") (name "Net-(R25-Pad1)") (class "Default")
      (node (ref "R25") (pin "1") (pinfunction "1_1") (pintype "passive"))
      (node (ref "SV5") (pin "7") (pinfunction "7_7") (pintype "passive"))
    )
    (net (code "102") (name "Net-(R30-Pad1)") (class "Default")
      (node (ref "R30") (pin "1") (pinfunction "1_1") (pintype "passive"))
      (node (ref "SV2") (pin "3") (pinfunction "3_3") (pintype "passive"))
    )
    (net (code "103") (name "Net-(R40-Pad2)") (class "Default")
      (node (ref "R40") (pin "2") (pinfunction "2_2") (pintype "passive"))
      (node (ref "R41") (pin "1") (pinfunction "1_1") (pintype "passive"))
      (node (ref "R42") (pin "1") (pinfunction "1_1") (pintype "passive"))
    )
    (net (code "104") (name "Net-(R48-Pad2)") (class "Default")
      (node (ref "R48") (pin "2") (pinfunction "2_2") (pintype "passive"))
      (node (ref "R49") (pin "1") (pinfunction "1_1") (pintype "passive"))
      (node (ref "R50") (pin "1") (pinfunction "1_1") (pintype "passive"))
    )
    (net (code "105") (name "Net-(R54-Pad1)") (class "Default")
      (node (ref "R54") (pin "1") (pinfunction "1_1") (pintype "passive"))
      (node (ref "SV6") (pin "3") (pinfunction "3_3") (pintype "passive"))
    )
    (net (code "106") (name "Net-(R64-Pad2)") (class "Default")
      (node (ref "R64") (pin "2") (pinfunction "2_2") (pintype "passive"))
      (node (ref "R65") (pin "1") (pinfunction "1_1") (pintype "passive"))
      (node (ref "R66") (pin "1") (pinfunction "1_1") (pintype "passive"))
    )
    (net (code "107") (name "Net-(SV1-Pad1)") (class "Default")
      (node (ref "SV1") (pin "1") (pinfunction "1_1") (pintype "passive"))
      (node (ref "SV1") (pin "6") (pinfunction "6_6") (pintype "passive"))
    )
    (net (code "108") (name "Net-(SV1-Pad2)") (class "Default")
      (node (ref "SV1") (pin "2") (pinfunction "2_2") (pintype "passive"))
      (node (ref "SV1") (pin "4") (pinfunction "4_4") (pintype "passive"))
    )
    (net (code "109") (name "Net-(SV1-Pad10)") (class "Default")
      (node (ref "SV1") (pin "10") (pinfunction "10_10") (pintype "passive"))
      (node (ref "SV1") (pin "8") (pinfunction "8_8") (pintype "passive"))
    )
    (net (code "110") (name "Net-(SV2-Pad2)") (class "Default")
      (node (ref "SV2") (pin "2") (pinfunction "2_2") (pintype "passive"))
      (node (ref "SV2") (pin "4") (pinfunction "4_4") (pintype "passive"))
    )
    (net (code "111") (name "Net-(SV2-Pad6)") (class "Default")
      (node (ref "SV2") (pin "6") (pinfunction "6_6") (pintype "passive"))
      (node (ref "SV2") (pin "9") (pinfunction "9_9") (pintype "passive"))
    )
    (net (code "112") (name "Net-(SV2-Pad10)") (class "Default")
      (node (ref "SV2") (pin "10") (pinfunction "10_10") (pintype "passive"))
      (node (ref "SV2") (pin "8") (pinfunction "8_8") (pintype "passive"))
    )
    (net (code "113") (name "Net-(SV3-Pad2)") (class "Default")
      (node (ref "SV3") (pin "2") (pinfunction "2_2") (pintype "passive"))
      (node (ref "SV3") (pin "3") (pinfunction "3_3") (pintype "passive"))
    )
    (net (code "114") (name "Net-(SV3-Pad5)") (class "Default")
      (node (ref "SV3") (pin "5") (pinfunction "5_5") (pintype "passive"))
      (node (ref "SV3") (pin "6") (pinfunction "6_6") (pintype "passive"))
    )
    (net (code "115") (name "Net-(SV3-Pad8)") (class "Default")
      (node (ref "SV3") (pin "8") (pinfunction "8_8") (pintype "passive"))
      (node (ref "SV3") (pin "9") (pinfunction "9_9") (pintype "passive"))
    )
    (net (code "116") (name "Net-(SV3-Pad11)") (class "Default")
      (node (ref "SV3") (pin "11") (pinfunction "11_11") (pintype "passive"))
      (node (ref "SV3") (pin "12") (pinfunction "12_12") (pintype "passive"))
    )
    (net (code "117") (name "Net-(SV3-Pad14)") (class "Default")
      (node (ref "SV3") (pin "14") (pinfunction "14_14") (pintype "passive"))
      (node (ref "SV3") (pin "15") (pinfunction "15_15") (pintype "passive"))
    )
    (net (code "118") (name "Net-(SV4-Pad2)") (class "Default")
      (node (ref "SV4") (pin "2") (pinfunction "2_2") (pintype "passive"))
      (node (ref "SV4") (pin "3") (pinfunction "3_3") (pintype "passive"))
    )
    (net (code "119") (name "Net-(SV4-Pad5)") (class "Default")
      (node (ref "SV4") (pin "5") (pinfunction "5_5") (pintype "passive"))
      (node (ref "SV4") (pin "6") (pinfunction "6_6") (pintype "passive"))
    )
    (net (code "120") (name "Net-(SV4-Pad8)") (class "Default")
      (node (ref "SV4") (pin "8") (pinfunction "8_8") (pintype "passive"))
      (node (ref "SV4") (pin "9") (pinfunction "9_9") (pintype "passive"))
    )
    (net (code "121") (name "Net-(SV4-Pad11)") (class "Default")
      (node (ref "SV4") (pin "11") (pinfunction "11_11") (pintype "passive"))
      (node (ref "SV4") (pin "12") (pinfunction "12_12") (pintype "passive"))
    )
    (net (code "122") (name "Net-(SV5-Pad1)") (class "Default")
      (node (ref "SV5") (pin "1") (pinfunction "1_1") (pintype "passive"))
      (node (ref "SV5") (pin "6") (pinfunction "6_6") (pintype "passive"))
    )
    (net (code "123") (name "Net-(SV5-Pad2)") (class "Default")
      (node (ref "SV5") (pin "2") (pinfunction "2_2") (pintype "passive"))
      (node (ref "SV5") (pin "4") (pinfunction "4_4") (pintype "passive"))
    )
    (net (code "124") (name "Net-(SV5-Pad10)") (class "Default")
      (node (ref "SV5") (pin "10") (pinfunction "10_10") (pintype "passive"))
      (node (ref "SV5") (pin "8") (pinfunction "8_8") (pintype "passive"))
    )
    (net (code "125") (name "Net-(SV6-Pad2)") (class "Default")
      (node (ref "SV6") (pin "2") (pinfunction "2_2") (pintype "passive"))
      (node (ref "SV6") (pin "4") (pinfunction "4_4") (pintype "passive"))
    )
    (net (code "126") (name "Net-(SV6-Pad6)") (class "Default")
      (node (ref "SV6") (pin "6") (pinfunction "6_6") (pintype "passive"))
      (node (ref "SV6") (pin "9") (pinfunction "9_9") (pintype "passive"))
    )
    (net (code "127") (name "Net-(SV6-Pad10)") (class "Default")
      (node (ref "SV6") (pin "10") (pinfunction "10_10") (pintype "passive"))
      (node (ref "SV6") (pin "8") (pinfunction "8_8") (pintype "passive"))
    )
    (net (code "128") (name "Net-(SV7-Pad2)") (class "Default")
      (node (ref "SV7") (pin "2") (pinfunction "2_2") (pintype "passive"))
      (node (ref "SV7") (pin "3") (pinfunction "3_3") (pintype "passive"))
    )
    (net (code "129") (name "Net-(SV7-Pad5)") (class "Default")
      (node (ref "SV7") (pin "5") (pinfunction "5_5") (pintype "passive"))
      (node (ref "SV7") (pin "6") (pinfunction "6_6") (pintype "passive"))
    )
    (net (code "130") (name "Net-(SV7-Pad8)") (class "Default")
      (node (ref "SV7") (pin "8") (pinfunction "8_8") (pintype "passive"))
      (node (ref "SV7") (pin "9") (pinfunction "9_9") (pintype "passive"))
    )
    (net (code "131") (name "Net-(SV7-Pad11)") (class "Default")
      (node (ref "SV7") (pin "11") (pinfunction "11_11") (pintype "passive"))
      (node (ref "SV7") (pin "12") (pinfunction "12_12") (pintype "passive"))
    )
    (net (code "132") (name "Net-(X1A-S)") (class "Default")
      (node (ref "JP2") (pin "2") (pinfunction "2_2") (pintype "passive"))
      (node (ref "R16") (pin "1") (pinfunction "1_1") (pintype "passive"))
      (node (ref "X1") (pin "1") (pinfunction "S_1") (pintype "passive"))
    )
    (net (code "133") (name "Net-(X1D-S)") (class "Default")
      (node (ref "JP1") (pin "1") (pinfunction "1_1") (pintype "passive"))
      (node (ref "R15") (pin "1") (pinfunction "1_1") (pintype "passive"))
      (node (ref "X1") (pin "4") (pinfunction "S_4") (pintype "passive"))
    )
    (net (code "134") (name "V+") (class "Default")
      (node (ref "C1") (pin "1") (pinfunction "1_1") (pintype "passive"))
      (node (ref "C10") (pin "1") (pinfunction "1_1") (pintype "passive"))
      (node (ref "C15") (pin "1") (pinfunction "1_1") (pintype "passive"))
      (node (ref "C16") (pin "1") (pinfunction "1_1") (pintype "passive"))
      (node (ref "C17") (pin "1") (pinfunction "1_1") (pintype "passive"))
      (node (ref "C18") (pin "1") (pinfunction "1_1") (pintype "passive"))
      (node (ref "C19") (pin "1") (pinfunction "1_1") (pintype "passive"))
      (node (ref "C2") (pin "1") (pinfunction "1_1") (pintype "passive"))
      (node (ref "C20") (pin "1") (pinfunction "1_1") (pintype "passive"))
      (node (ref "C3") (pin "1") (pinfunction "1_1") (pintype "passive"))
      (node (ref "C4") (pin "1") (pinfunction "1_1") (pintype "passive"))
      (node (ref "C5") (pin "+") (pinfunction "+_+") (pintype "passive"))
      (node (ref "C9") (pin "1") (pinfunction "1_1") (pintype "passive"))
      (node (ref "IC1") (pin "14") (pinfunction "VDD_14") (pintype "power_in"))
      (node (ref "IC12") (pin "14") (pinfunction "VDD_14") (pintype "power_in"))
      (node (ref "IC3") (pin "1") (pinfunction "VDD_1") (pintype "power_in"))
      (node (ref "IC6") (pin "14") (pinfunction "VDD_14") (pintype "power_in"))
      (node (ref "IC7") (pin "1") (pinfunction "VDD_1") (pintype "power_in"))
      (node (ref "IC8") (pin "14") (pinfunction "VDD_14") (pintype "power_in"))
      (node (ref "JP3") (pin "1") (pinfunction "1_1") (pintype "passive"))
      (node (ref "R15") (pin "2") (pinfunction "2_2") (pintype "passive"))
    )
    (net (code "135") (name "V-") (class "Default")
      (node (ref "C10") (pin "2") (pinfunction "2_2") (pintype "passive"))
      (node (ref "C15") (pin "2") (pinfunction "2_2") (pintype "passive"))
      (node (ref "C18") (pin "2") (pinfunction "2_2") (pintype "passive"))
      (node (ref "C20") (pin "2") (pinfunction "2_2") (pintype "passive"))
      (node (ref "C3") (pin "2") (pinfunction "2_2") (pintype "passive"))
      (node (ref "C4") (pin "2") (pinfunction "2_2") (pintype "passive"))
      (node (ref "C6") (pin "-") (pinfunction "-_-") (pintype "passive"))
      (node (ref "JP4") (pin "2") (pinfunction "2_2") (pintype "passive"))
      (node (ref "R16") (pin "2") (pinfunction "2_2") (pintype "passive"))
    )
    (net (code "136") (name "unconnected-(R1-E-Pad3)") (class "Default")
      (node (ref "R1") (pin "3") (pinfunction "E_3") (pintype "passive"))
    )
    (net (code "137") (name "unconnected-(R17-E-Pad3)") (class "Default")
      (node (ref "R17") (pin "3") (pinfunction "E_3") (pintype "passive"))
    )
    (net (code "138") (name "unconnected-(R39-E-Pad3)") (class "Default")
      (node (ref "R39") (pin "3") (pinfunction "E_3") (pintype "passive"))
    )
    (net (code "139") (name "unconnected-(R63-E-Pad3)") (class "Default")
      (node (ref "R63") (pin "3") (pinfunction "E_3") (pintype "passive"))
    )
    (net (code "140") (name "unconnected-(SV1-Pad9)") (class "Default")
      (node (ref "SV1") (pin "9") (pinfunction "9_9") (pintype "passive"))
    )
    (net (code "141") (name "unconnected-(SV2-Pad1)") (class "Default")
      (node (ref "SV2") (pin "1") (pinfunction "1_1") (pintype "passive"))
    )
    (net (code "142") (name "unconnected-(SV5-Pad9)") (class "Default")
      (node (ref "SV5") (pin "9") (pinfunction "9_9") (pintype "passive"))
    )
    (net (code "143") (name "unconnected-(SV6-Pad1)") (class "Default")
      (node (ref "SV6") (pin "1") (pinfunction "1_1") (pintype "passive"))
    )
  )
)
